# SCH_TrailCheaper_2024-05-25.net
KiCad netlist of a schematic drawn in EasyEDA
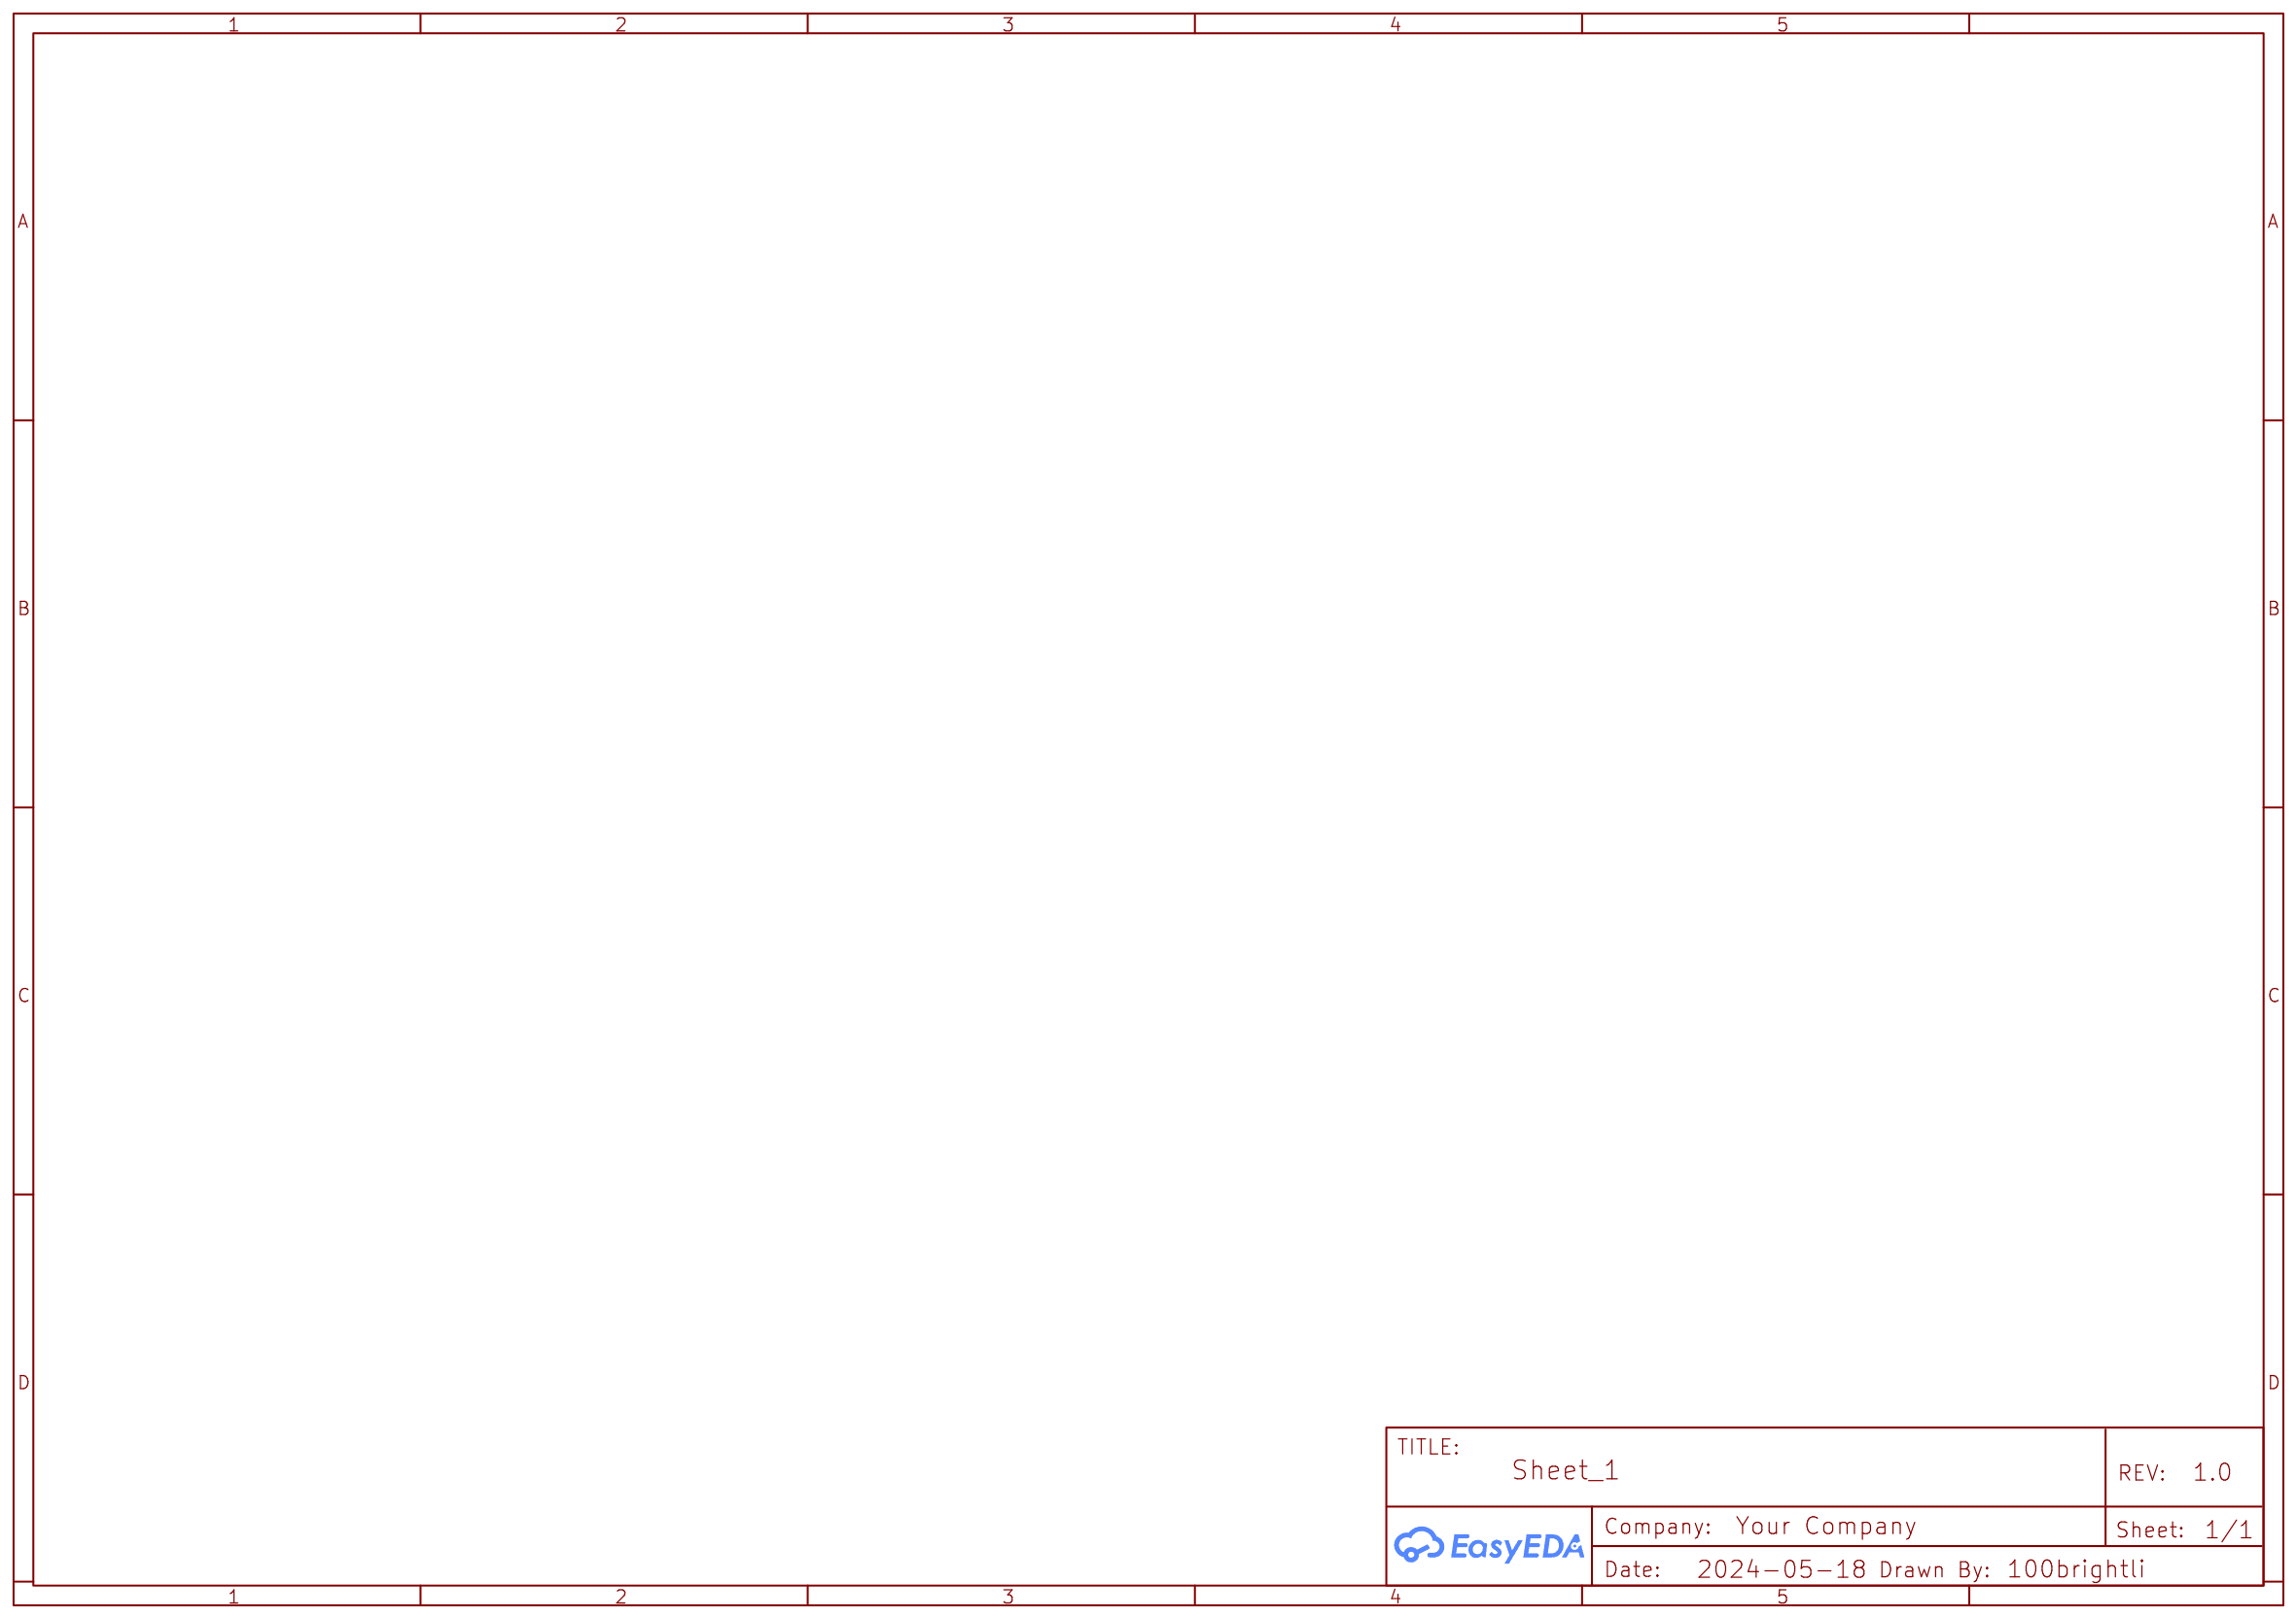
[diagram p0: Sheet_1]
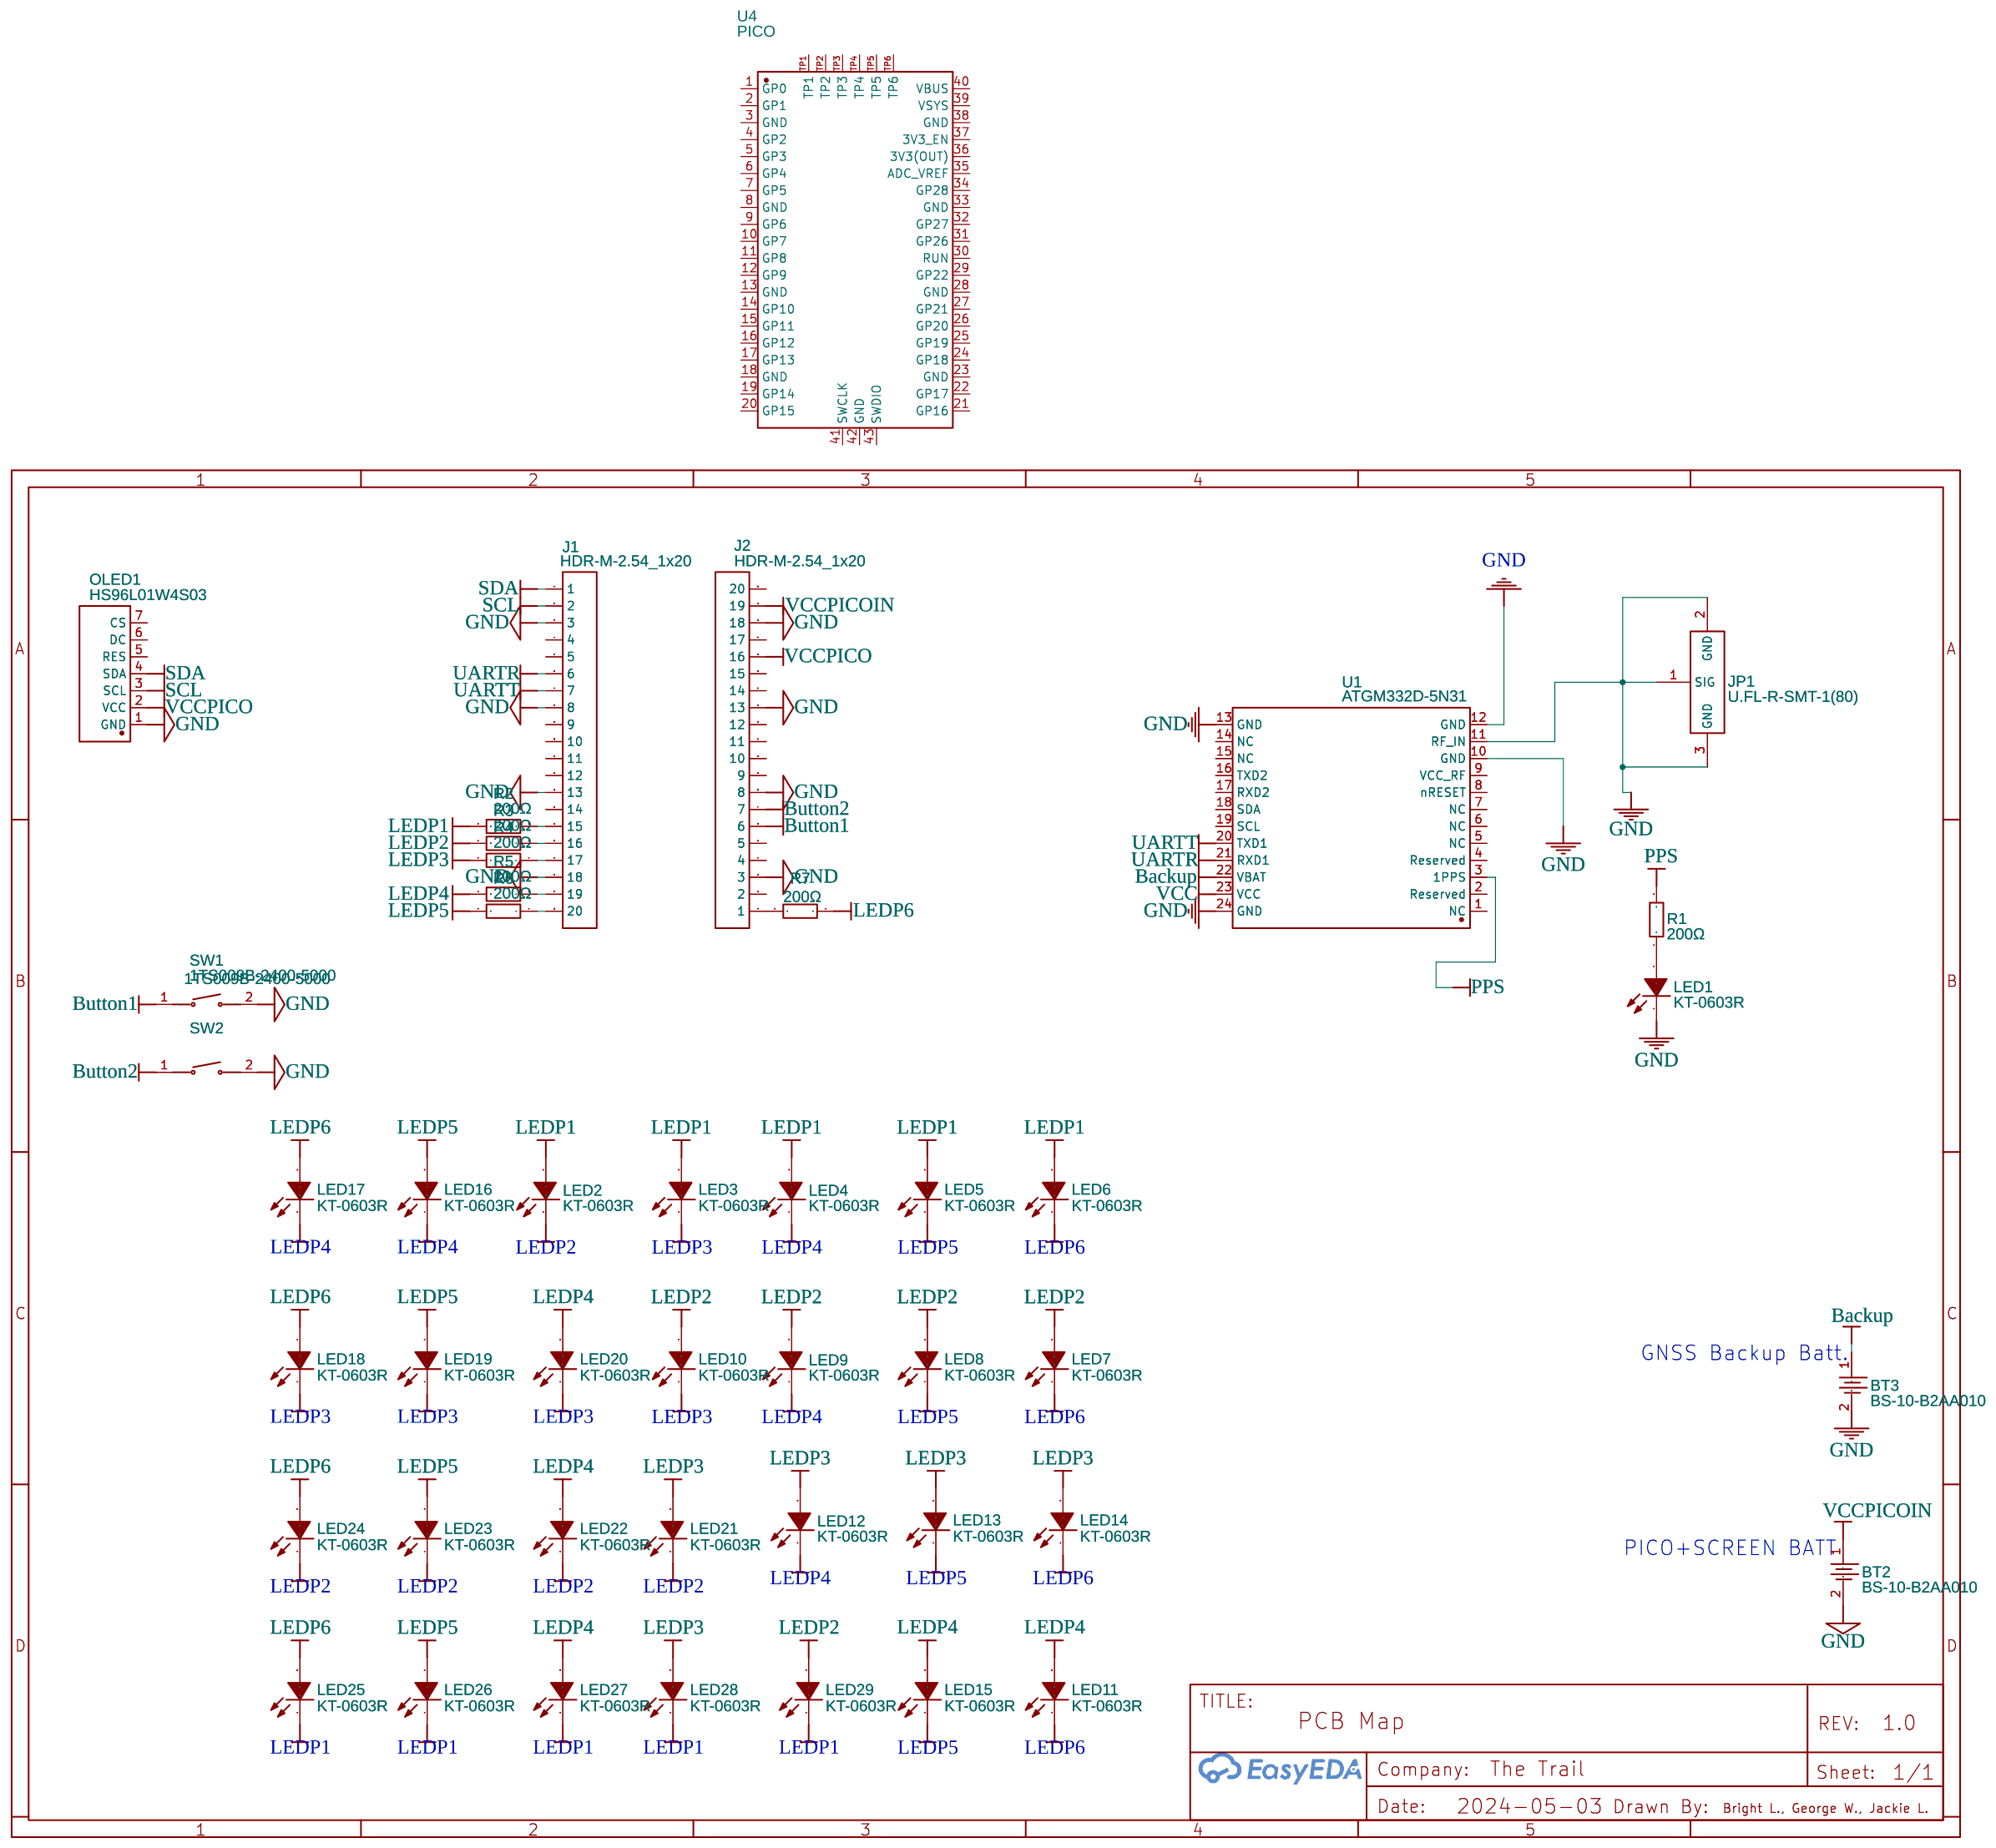
[diagram p1: Sheet_2_Cheaper? copy]

(export (version "E")
  (design (tool "Eeschema 10.0.6"))
  (components
    (comp (ref "BT2")
      (value "BS-10-B2AA010")
      (fields (field (name "Manufacturer") "MYOUNG(美阳)"))
      (libsource (lib "") (part "BS-10-B2AA010"))
    )
    (comp (ref "BT3")
      (value "BS-10-B2AA010")
      (fields (field (name "Manufacturer") "MYOUNG(美阳)"))
      (libsource (lib "") (part "BS-10-B2AA010"))
    )
    (comp (ref "J1") (value "HDR-M-2.54_1x20") (libsource (lib "") (part "HDR-M-2.54_1x20")))
    (comp (ref "J2") (value "HDR-M-2.54_1x20") (libsource (lib "") (part "HDR-M-2.54_1x20_1")))
    (comp (ref "JP1")
      (value "U.FL-R-SMT-1(80)")
      (fields (field (name "Manufacturer") "HRS(广濑)"))
      (libsource (lib "") (part "U.FL-R-SMT-1(80)"))
    )
    (comp (ref "LED1")
      (value "KT-0603R")
      (fields (field (name "Manufacturer") "KENTO"))
      (libsource (lib "") (part "KT-0603R"))
    )
    (comp (ref "LED2")
      (value "KT-0603R")
      (fields (field (name "Manufacturer") "KENTO"))
      (libsource (lib "") (part "KT-0603R"))
    )
    (comp (ref "LED3")
      (value "KT-0603R")
      (fields (field (name "Manufacturer") "KENTO"))
      (libsource (lib "") (part "KT-0603R"))
    )
    (comp (ref "LED4")
      (value "KT-0603R")
      (fields (field (name "Manufacturer") "KENTO"))
      (libsource (lib "") (part "KT-0603R"))
    )
    (comp (ref "LED5")
      (value "KT-0603R")
      (fields (field (name "Manufacturer") "KENTO"))
      (libsource (lib "") (part "KT-0603R"))
    )
    (comp (ref "LED6")
      (value "KT-0603R")
      (fields (field (name "Manufacturer") "KENTO"))
      (libsource (lib "") (part "KT-0603R"))
    )
    (comp (ref "LED7")
      (value "KT-0603R")
      (fields (field (name "Manufacturer") "KENTO"))
      (libsource (lib "") (part "KT-0603R"))
    )
    (comp (ref "LED8")
      (value "KT-0603R")
      (fields (field (name "Manufacturer") "KENTO"))
      (libsource (lib "") (part "KT-0603R"))
    )
    (comp (ref "LED9")
      (value "KT-0603R")
      (fields (field (name "Manufacturer") "KENTO"))
      (libsource (lib "") (part "KT-0603R"))
    )
    (comp (ref "LED10")
      (value "KT-0603R")
      (fields (field (name "Manufacturer") "KENTO"))
      (libsource (lib "") (part "KT-0603R"))
    )
    (comp (ref "LED11")
      (value "KT-0603R")
      (fields (field (name "Manufacturer") "KENTO"))
      (libsource (lib "") (part "KT-0603R"))
    )
    (comp (ref "LED12")
      (value "KT-0603R")
      (fields (field (name "Manufacturer") "KENTO"))
      (libsource (lib "") (part "KT-0603R"))
    )
    (comp (ref "LED13")
      (value "KT-0603R")
      (fields (field (name "Manufacturer") "KENTO"))
      (libsource (lib "") (part "KT-0603R"))
    )
    (comp (ref "LED14")
      (value "KT-0603R")
      (fields (field (name "Manufacturer") "KENTO"))
      (libsource (lib "") (part "KT-0603R"))
    )
    (comp (ref "LED15")
      (value "KT-0603R")
      (fields (field (name "Manufacturer") "KENTO"))
      (libsource (lib "") (part "KT-0603R"))
    )
    (comp (ref "LED16")
      (value "KT-0603R")
      (fields (field (name "Manufacturer") "KENTO"))
      (libsource (lib "") (part "KT-0603R"))
    )
    (comp (ref "LED17")
      (value "KT-0603R")
      (fields (field (name "Manufacturer") "KENTO"))
      (libsource (lib "") (part "KT-0603R"))
    )
    (comp (ref "LED18")
      (value "KT-0603R")
      (fields (field (name "Manufacturer") "KENTO"))
      (libsource (lib "") (part "KT-0603R"))
    )
    (comp (ref "LED19")
      (value "KT-0603R")
      (fields (field (name "Manufacturer") "KENTO"))
      (libsource (lib "") (part "KT-0603R"))
    )
    (comp (ref "LED20")
      (value "KT-0603R")
      (fields (field (name "Manufacturer") "KENTO"))
      (libsource (lib "") (part "KT-0603R"))
    )
    (comp (ref "LED21")
      (value "KT-0603R")
      (fields (field (name "Manufacturer") "KENTO"))
      (libsource (lib "") (part "KT-0603R"))
    )
    (comp (ref "LED22")
      (value "KT-0603R")
      (fields (field (name "Manufacturer") "KENTO"))
      (libsource (lib "") (part "KT-0603R"))
    )
    (comp (ref "LED23")
      (value "KT-0603R")
      (fields (field (name "Manufacturer") "KENTO"))
      (libsource (lib "") (part "KT-0603R"))
    )
    (comp (ref "LED24")
      (value "KT-0603R")
      (fields (field (name "Manufacturer") "KENTO"))
      (libsource (lib "") (part "KT-0603R"))
    )
    (comp (ref "LED25")
      (value "KT-0603R")
      (fields (field (name "Manufacturer") "KENTO"))
      (libsource (lib "") (part "KT-0603R"))
    )
    (comp (ref "LED26")
      (value "KT-0603R")
      (fields (field (name "Manufacturer") "KENTO"))
      (libsource (lib "") (part "KT-0603R"))
    )
    (comp (ref "LED27")
      (value "KT-0603R")
      (fields (field (name "Manufacturer") "KENTO"))
      (libsource (lib "") (part "KT-0603R"))
    )
    (comp (ref "LED28")
      (value "KT-0603R")
      (fields (field (name "Manufacturer") "KENTO"))
      (libsource (lib "") (part "KT-0603R"))
    )
    (comp (ref "LED29")
      (value "KT-0603R")
      (fields (field (name "Manufacturer") "KENTO"))
      (libsource (lib "") (part "KT-0603R"))
    )
    (comp (ref "OLED1")
      (value "HS96L01W4S03")
      (fields (field (name "Manufacturer") "HS(汉昇)"))
      (libsource (lib "") (part "HS96L01W4S03"))
    )
    (comp (ref "R1")
      (value "200Ω")
      (fields
        (field (name "Manufacturer Part") "0402WGF2000TCE")
        (field (name "Manufacturer") "UNI-ROYAL(厚声)")
      )
      (libsource (lib "") (part "0402WGF2000TCE_1"))
    )
    (comp (ref "R2")
      (value "200Ω")
      (fields
        (field (name "Manufacturer Part") "0402WGF2000TCE")
        (field (name "Manufacturer") "UNI-ROYAL(厚声)")
      )
      (libsource (lib "") (part "0402WGF2000TCE"))
    )
    (comp (ref "R3")
      (value "200Ω")
      (fields
        (field (name "Manufacturer Part") "0402WGF2000TCE")
        (field (name "Manufacturer") "UNI-ROYAL(厚声)")
      )
      (libsource (lib "") (part "0402WGF2000TCE"))
    )
    (comp (ref "R4")
      (value "200Ω")
      (fields
        (field (name "Manufacturer Part") "0402WGF2000TCE")
        (field (name "Manufacturer") "UNI-ROYAL(厚声)")
      )
      (libsource (lib "") (part "0402WGF2000TCE"))
    )
    (comp (ref "R5")
      (value "200Ω")
      (fields
        (field (name "Manufacturer Part") "0402WGF2000TCE")
        (field (name "Manufacturer") "UNI-ROYAL(厚声)")
      )
      (libsource (lib "") (part "0402WGF2000TCE"))
    )
    (comp (ref "R6")
      (value "200Ω")
      (fields
        (field (name "Manufacturer Part") "0402WGF2000TCE")
        (field (name "Manufacturer") "UNI-ROYAL(厚声)")
      )
      (libsource (lib "") (part "0402WGF2000TCE"))
    )
    (comp (ref "R7")
      (value "200Ω")
      (fields
        (field (name "Manufacturer Part") "0402WGF2000TCE")
        (field (name "Manufacturer") "UNI-ROYAL(厚声)")
      )
      (libsource (lib "") (part "0402WGF2000TCE"))
    )
    (comp (ref "SW1")
      (value "1TS009B-2400-5000")
      (fields
        (field (name "Manufacturer Part") "1TS009B-2400-5000-CT")
        (field (name "Manufacturer") "HYP(鸿源精密)")
      )
      (libsource (lib "") (part "1TS009B-2400-5000"))
    )
    (comp (ref "SW2")
      (value "1TS009B-2400-5000")
      (fields
        (field (name "Manufacturer Part") "1TS009B-2400-5000-CT")
        (field (name "Manufacturer") "HYP(鸿源精密)")
      )
      (libsource (lib "") (part "1TS009B-2400-5000"))
    )
    (comp (ref "U1")
      (value "ATGM332D-5N31")
      (fields (field (name "Manufacturer") "杭州中科微"))
      (libsource (lib "") (part "ATGM332D-5N31"))
    )
    (comp (ref "U4")
      (value "PICO")
      (fields (field (name "Manufacturer") "Raspberry Pi(树莓派)"))
      (libsource (lib "") (part "PICO"))
    )
  )
  (nets
    (net (code "1") (name "Backup") (class "Default")
      (node (ref "BT3") (pin "1") (pinfunction "1_1") (pintype "input"))
      (node (ref "U1") (pin "22") (pinfunction "VBAT_22") (pintype "unspecified"))
    )
    (net (code "2") (name "Button1") (class "Default")
      (node (ref "J2") (pin "6") (pinfunction "6_6") (pintype "unspecified"))
      (node (ref "SW1") (pin "1") (pinfunction "1_1") (pintype "unspecified"))
    )
    (net (code "3") (name "Button2") (class "Default")
      (node (ref "J2") (pin "7") (pinfunction "7_7") (pintype "unspecified"))
      (node (ref "SW2") (pin "1") (pinfunction "1_1") (pintype "unspecified"))
    )
    (net (code "4") (name "GND") (class "Default")
      (node (ref "BT2") (pin "2") (pinfunction "2_2") (pintype "input"))
      (node (ref "BT3") (pin "2") (pinfunction "2_2") (pintype "input"))
      (node (ref "J1") (pin "13") (pinfunction "13_13") (pintype "unspecified"))
      (node (ref "J1") (pin "18") (pinfunction "18_18") (pintype "unspecified"))
      (node (ref "J1") (pin "3") (pinfunction "3_3") (pintype "unspecified"))
      (node (ref "J1") (pin "8") (pinfunction "8_8") (pintype "unspecified"))
      (node (ref "J2") (pin "13") (pinfunction "13_13") (pintype "unspecified"))
      (node (ref "J2") (pin "18") (pinfunction "18_18") (pintype "unspecified"))
      (node (ref "J2") (pin "3") (pinfunction "3_3") (pintype "unspecified"))
      (node (ref "J2") (pin "8") (pinfunction "8_8") (pintype "unspecified"))
      (node (ref "JP1") (pin "1") (pinfunction "SIG_1") (pintype "unspecified"))
      (node (ref "JP1") (pin "2") (pinfunction "GND_2") (pintype "unspecified"))
      (node (ref "JP1") (pin "3") (pinfunction "GND_3") (pintype "unspecified"))
      (node (ref "LED1") (pin "1") (pinfunction "K_1") (pintype "unspecified"))
      (node (ref "OLED1") (pin "1") (pinfunction "GND_1") (pintype "unspecified"))
      (node (ref "SW1") (pin "2") (pinfunction "2_2") (pintype "unspecified"))
      (node (ref "SW2") (pin "2") (pinfunction "2_2") (pintype "unspecified"))
      (node (ref "U1") (pin "10") (pinfunction "GND_10") (pintype "unspecified"))
      (node (ref "U1") (pin "11") (pinfunction "RF_IN_11") (pintype "unspecified"))
      (node (ref "U1") (pin "12") (pinfunction "GND_12") (pintype "unspecified"))
      (node (ref "U1") (pin "13") (pinfunction "GND_13") (pintype "unspecified"))
      (node (ref "U1") (pin "24") (pinfunction "GND_24") (pintype "unspecified"))
    )
    (net (code "5") (name "LEDP1") (class "Default")
      (node (ref "LED2") (pin "2") (pinfunction "A_2") (pintype "unspecified"))
      (node (ref "LED25") (pin "1") (pinfunction "K_1") (pintype "unspecified"))
      (node (ref "LED26") (pin "1") (pinfunction "K_1") (pintype "unspecified"))
      (node (ref "LED27") (pin "1") (pinfunction "K_1") (pintype "unspecified"))
      (node (ref "LED28") (pin "1") (pinfunction "K_1") (pintype "unspecified"))
      (node (ref "LED29") (pin "1") (pinfunction "K_1") (pintype "unspecified"))
      (node (ref "LED3") (pin "2") (pinfunction "A_2") (pintype "unspecified"))
      (node (ref "LED4") (pin "2") (pinfunction "A_2") (pintype "unspecified"))
      (node (ref "LED5") (pin "2") (pinfunction "A_2") (pintype "unspecified"))
      (node (ref "LED6") (pin "2") (pinfunction "A_2") (pintype "unspecified"))
      (node (ref "R2") (pin "2") (pinfunction "2_2") (pintype "input"))
    )
    (net (code "6") (name "LEDP2") (class "Default")
      (node (ref "LED10") (pin "2") (pinfunction "A_2") (pintype "unspecified"))
      (node (ref "LED2") (pin "1") (pinfunction "K_1") (pintype "unspecified"))
      (node (ref "LED21") (pin "1") (pinfunction "K_1") (pintype "unspecified"))
      (node (ref "LED22") (pin "1") (pinfunction "K_1") (pintype "unspecified"))
      (node (ref "LED23") (pin "1") (pinfunction "K_1") (pintype "unspecified"))
      (node (ref "LED24") (pin "1") (pinfunction "K_1") (pintype "unspecified"))
      (node (ref "LED29") (pin "2") (pinfunction "A_2") (pintype "unspecified"))
      (node (ref "LED7") (pin "2") (pinfunction "A_2") (pintype "unspecified"))
      (node (ref "LED8") (pin "2") (pinfunction "A_2") (pintype "unspecified"))
      (node (ref "LED9") (pin "2") (pinfunction "A_2") (pintype "unspecified"))
      (node (ref "R3") (pin "2") (pinfunction "2_2") (pintype "input"))
    )
    (net (code "7") (name "LEDP3") (class "Default")
      (node (ref "LED10") (pin "1") (pinfunction "K_1") (pintype "unspecified"))
      (node (ref "LED12") (pin "2") (pinfunction "A_2") (pintype "unspecified"))
      (node (ref "LED13") (pin "2") (pinfunction "A_2") (pintype "unspecified"))
      (node (ref "LED14") (pin "2") (pinfunction "A_2") (pintype "unspecified"))
      (node (ref "LED18") (pin "1") (pinfunction "K_1") (pintype "unspecified"))
      (node (ref "LED19") (pin "1") (pinfunction "K_1") (pintype "unspecified"))
      (node (ref "LED20") (pin "1") (pinfunction "K_1") (pintype "unspecified"))
      (node (ref "LED21") (pin "2") (pinfunction "A_2") (pintype "unspecified"))
      (node (ref "LED28") (pin "2") (pinfunction "A_2") (pintype "unspecified"))
      (node (ref "LED3") (pin "1") (pinfunction "K_1") (pintype "unspecified"))
      (node (ref "R4") (pin "2") (pinfunction "2_2") (pintype "input"))
    )
    (net (code "8") (name "LEDP4") (class "Default")
      (node (ref "LED11") (pin "2") (pinfunction "A_2") (pintype "unspecified"))
      (node (ref "LED12") (pin "1") (pinfunction "K_1") (pintype "unspecified"))
      (node (ref "LED15") (pin "2") (pinfunction "A_2") (pintype "unspecified"))
      (node (ref "LED16") (pin "1") (pinfunction "K_1") (pintype "unspecified"))
      (node (ref "LED17") (pin "1") (pinfunction "K_1") (pintype "unspecified"))
      (node (ref "LED20") (pin "2") (pinfunction "A_2") (pintype "unspecified"))
      (node (ref "LED22") (pin "2") (pinfunction "A_2") (pintype "unspecified"))
      (node (ref "LED27") (pin "2") (pinfunction "A_2") (pintype "unspecified"))
      (node (ref "LED4") (pin "1") (pinfunction "K_1") (pintype "unspecified"))
      (node (ref "LED9") (pin "1") (pinfunction "K_1") (pintype "unspecified"))
      (node (ref "R5") (pin "2") (pinfunction "2_2") (pintype "input"))
    )
    (net (code "9") (name "LEDP5") (class "Default")
      (node (ref "LED13") (pin "1") (pinfunction "K_1") (pintype "unspecified"))
      (node (ref "LED15") (pin "1") (pinfunction "K_1") (pintype "unspecified"))
      (node (ref "LED16") (pin "2") (pinfunction "A_2") (pintype "unspecified"))
      (node (ref "LED19") (pin "2") (pinfunction "A_2") (pintype "unspecified"))
      (node (ref "LED23") (pin "2") (pinfunction "A_2") (pintype "unspecified"))
      (node (ref "LED26") (pin "2") (pinfunction "A_2") (pintype "unspecified"))
      (node (ref "LED5") (pin "1") (pinfunction "K_1") (pintype "unspecified"))
      (node (ref "LED8") (pin "1") (pinfunction "K_1") (pintype "unspecified"))
      (node (ref "R6") (pin "2") (pinfunction "2_2") (pintype "input"))
    )
    (net (code "10") (name "LEDP6") (class "Default")
      (node (ref "LED11") (pin "1") (pinfunction "K_1") (pintype "unspecified"))
      (node (ref "LED14") (pin "1") (pinfunction "K_1") (pintype "unspecified"))
      (node (ref "LED17") (pin "2") (pinfunction "A_2") (pintype "unspecified"))
      (node (ref "LED18") (pin "2") (pinfunction "A_2") (pintype "unspecified"))
      (node (ref "LED24") (pin "2") (pinfunction "A_2") (pintype "unspecified"))
      (node (ref "LED25") (pin "2") (pinfunction "A_2") (pintype "unspecified"))
      (node (ref "LED6") (pin "1") (pinfunction "K_1") (pintype "unspecified"))
      (node (ref "LED7") (pin "1") (pinfunction "K_1") (pintype "unspecified"))
      (node (ref "R7") (pin "1") (pinfunction "1_1") (pintype "input"))
    )
    (net (code "11") (name "Net-(J1-Pad15)") (class "Default")
      (node (ref "J1") (pin "15") (pinfunction "15_15") (pintype "unspecified"))
      (node (ref "R2") (pin "1") (pinfunction "1_1") (pintype "input"))
    )
    (net (code "12") (name "Net-(J1-Pad16)") (class "Default")
      (node (ref "J1") (pin "16") (pinfunction "16_16") (pintype "unspecified"))
      (node (ref "R3") (pin "1") (pinfunction "1_1") (pintype "input"))
    )
    (net (code "13") (name "Net-(J1-Pad17)") (class "Default")
      (node (ref "J1") (pin "17") (pinfunction "17_17") (pintype "unspecified"))
      (node (ref "R4") (pin "1") (pinfunction "1_1") (pintype "input"))
    )
    (net (code "14") (name "Net-(J1-Pad19)") (class "Default")
      (node (ref "J1") (pin "19") (pinfunction "19_19") (pintype "unspecified"))
      (node (ref "R5") (pin "1") (pinfunction "1_1") (pintype "input"))
    )
    (net (code "15") (name "Net-(J1-Pad20)") (class "Default")
      (node (ref "J1") (pin "20") (pinfunction "20_20") (pintype "unspecified"))
      (node (ref "R6") (pin "1") (pinfunction "1_1") (pintype "input"))
    )
    (net (code "16") (name "Net-(J2-Pad1)") (class "Default")
      (node (ref "J2") (pin "1") (pinfunction "1_1") (pintype "unspecified"))
      (node (ref "R7") (pin "2") (pinfunction "2_2") (pintype "input"))
    )
    (net (code "17") (name "Net-(LED1-A)") (class "Default")
      (node (ref "LED1") (pin "2") (pinfunction "A_2") (pintype "unspecified"))
      (node (ref "R1") (pin "1") (pinfunction "1_1") (pintype "input"))
    )
    (net (code "18") (name "PPS") (class "Default")
      (node (ref "R1") (pin "2") (pinfunction "2_2") (pintype "input"))
      (node (ref "U1") (pin "3") (pinfunction "1PPS_3") (pintype "unspecified"))
    )
    (net (code "19") (name "SCL") (class "Default")
      (node (ref "J1") (pin "2") (pinfunction "2_2") (pintype "unspecified"))
      (node (ref "OLED1") (pin "3") (pinfunction "SCL_3") (pintype "unspecified"))
    )
    (net (code "20") (name "SDA") (class "Default")
      (node (ref "J1") (pin "1") (pinfunction "1_1") (pintype "unspecified"))
      (node (ref "OLED1") (pin "4") (pinfunction "SDA_4") (pintype "unspecified"))
    )
    (net (code "21") (name "UARTR") (class "Default")
      (node (ref "J1") (pin "6") (pinfunction "6_6") (pintype "unspecified"))
      (node (ref "U1") (pin "21") (pinfunction "RXD1_21") (pintype "unspecified"))
    )
    (net (code "22") (name "UARTT") (class "Default")
      (node (ref "J1") (pin "7") (pinfunction "7_7") (pintype "unspecified"))
      (node (ref "U1") (pin "20") (pinfunction "TXD1_20") (pintype "unspecified"))
    )
    (net (code "23") (name "VCC") (class "Default")
      (node (ref "U1") (pin "23") (pinfunction "VCC_23") (pintype "unspecified"))
    )
    (net (code "24") (name "VCCPICO") (class "Default")
      (node (ref "J2") (pin "16") (pinfunction "16_16") (pintype "unspecified"))
      (node (ref "OLED1") (pin "2") (pinfunction "VCC_2") (pintype "unspecified"))
    )
    (net (code "25") (name "VCCPICOIN") (class "Default")
      (node (ref "BT2") (pin "1") (pinfunction "1_1") (pintype "input"))
      (node (ref "J2") (pin "19") (pinfunction "19_19") (pintype "unspecified"))
    )
    (net (code "26") (name "unconnected-(J1-Pad4)") (class "Default")
      (node (ref "J1") (pin "4") (pinfunction "4_4") (pintype "unspecified"))
    )
    (net (code "27") (name "unconnected-(J1-Pad5)") (class "Default")
      (node (ref "J1") (pin "5") (pinfunction "5_5") (pintype "unspecified"))
    )
    (net (code "28") (name "unconnected-(J1-Pad9)") (class "Default")
      (node (ref "J1") (pin "9") (pinfunction "9_9") (pintype "unspecified"))
    )
    (net (code "29") (name "unconnected-(J1-Pad10)") (class "Default")
      (node (ref "J1") (pin "10") (pinfunction "10_10") (pintype "unspecified"))
    )
    (net (code "30") (name "unconnected-(J1-Pad11)") (class "Default")
      (node (ref "J1") (pin "11") (pinfunction "11_11") (pintype "unspecified"))
    )
    (net (code "31") (name "unconnected-(J1-Pad12)") (class "Default")
      (node (ref "J1") (pin "12") (pinfunction "12_12") (pintype "unspecified"))
    )
    (net (code "32") (name "unconnected-(J1-Pad14)") (class "Default")
      (node (ref "J1") (pin "14") (pinfunction "14_14") (pintype "unspecified"))
    )
    (net (code "33") (name "unconnected-(J2-Pad2)") (class "Default")
      (node (ref "J2") (pin "2") (pinfunction "2_2") (pintype "unspecified"))
    )
    (net (code "34") (name "unconnected-(J2-Pad4)") (class "Default")
      (node (ref "J2") (pin "4") (pinfunction "4_4") (pintype "unspecified"))
    )
    (net (code "35") (name "unconnected-(J2-Pad5)") (class "Default")
      (node (ref "J2") (pin "5") (pinfunction "5_5") (pintype "unspecified"))
    )
    (net (code "36") (name "unconnected-(J2-Pad9)") (class "Default")
      (node (ref "J2") (pin "9") (pinfunction "9_9") (pintype "unspecified"))
    )
    (net (code "37") (name "unconnected-(J2-Pad10)") (class "Default")
      (node (ref "J2") (pin "10") (pinfunction "10_10") (pintype "unspecified"))
    )
    (net (code "38") (name "unconnected-(J2-Pad11)") (class "Default")
      (node (ref "J2") (pin "11") (pinfunction "11_11") (pintype "unspecified"))
    )
    (net (code "39") (name "unconnected-(J2-Pad12)") (class "Default")
      (node (ref "J2") (pin "12") (pinfunction "12_12") (pintype "unspecified"))
    )
    (net (code "40") (name "unconnected-(J2-Pad14)") (class "Default")
      (node (ref "J2") (pin "14") (pinfunction "14_14") (pintype "unspecified"))
    )
    (net (code "41") (name "unconnected-(J2-Pad15)") (class "Default")
      (node (ref "J2") (pin "15") (pinfunction "15_15") (pintype "unspecified"))
    )
    (net (code "42") (name "unconnected-(J2-Pad17)") (class "Default")
      (node (ref "J2") (pin "17") (pinfunction "17_17") (pintype "unspecified"))
    )
    (net (code "43") (name "unconnected-(J2-Pad20)") (class "Default")
      (node (ref "J2") (pin "20") (pinfunction "20_20") (pintype "unspecified"))
    )
    (net (code "44") (name "unconnected-(OLED1-CS-Pad7)") (class "Default")
      (node (ref "OLED1") (pin "7") (pinfunction "CS_7") (pintype "unspecified"))
    )
    (net (code "45") (name "unconnected-(OLED1-DC-Pad6)") (class "Default")
      (node (ref "OLED1") (pin "6") (pinfunction "DC_6") (pintype "unspecified"))
    )
    (net (code "46") (name "unconnected-(OLED1-RES-Pad5)") (class "Default")
      (node (ref "OLED1") (pin "5") (pinfunction "RES_5") (pintype "unspecified"))
    )
    (net (code "47") (name "unconnected-(U1-NC-Pad1)") (class "Default")
      (node (ref "U1") (pin "1") (pinfunction "NC_1") (pintype "unspecified"))
    )
    (net (code "48") (name "unconnected-(U1-NC-Pad5)") (class "Default")
      (node (ref "U1") (pin "5") (pinfunction "NC_5") (pintype "unspecified"))
    )
    (net (code "49") (name "unconnected-(U1-NC-Pad6)") (class "Default")
      (node (ref "U1") (pin "6") (pinfunction "NC_6") (pintype "unspecified"))
    )
    (net (code "50") (name "unconnected-(U1-NC-Pad7)") (class "Default")
      (node (ref "U1") (pin "7") (pinfunction "NC_7") (pintype "unspecified"))
    )
    (net (code "51") (name "unconnected-(U1-NC-Pad14)") (class "Default")
      (node (ref "U1") (pin "14") (pinfunction "NC_14") (pintype "unspecified"))
    )
    (net (code "52") (name "unconnected-(U1-NC-Pad15)") (class "Default")
      (node (ref "U1") (pin "15") (pinfunction "NC_15") (pintype "unspecified"))
    )
    (net (code "53") (name "unconnected-(U1-RXD2-Pad17)") (class "Default")
      (node (ref "U1") (pin "17") (pinfunction "RXD2_17") (pintype "unspecified"))
    )
    (net (code "54") (name "unconnected-(U1-Reserved-Pad2)") (class "Default")
      (node (ref "U1") (pin "2") (pinfunction "Reserved_2") (pintype "unspecified"))
    )
    (net (code "55") (name "unconnected-(U1-Reserved-Pad4)") (class "Default")
      (node (ref "U1") (pin "4") (pinfunction "Reserved_4") (pintype "unspecified"))
    )
    (net (code "56") (name "unconnected-(U1-SCL-Pad19)") (class "Default")
      (node (ref "U1") (pin "19") (pinfunction "SCL_19") (pintype "unspecified"))
    )
    (net (code "57") (name "unconnected-(U1-SDA-Pad18)") (class "Default")
      (node (ref "U1") (pin "18") (pinfunction "SDA_18") (pintype "unspecified"))
    )
    (net (code "58") (name "unconnected-(U1-TXD2-Pad16)") (class "Default")
      (node (ref "U1") (pin "16") (pinfunction "TXD2_16") (pintype "unspecified"))
    )
    (net (code "59") (name "unconnected-(U1-VCC_RF-Pad9)") (class "Default")
      (node (ref "U1") (pin "9") (pinfunction "VCC_RF_9") (pintype "unspecified"))
    )
    (net (code "60") (name "unconnected-(U1-nRESET-Pad8)") (class "Default")
      (node (ref "U1") (pin "8") (pinfunction "nRESET_8") (pintype "unspecified"))
    )
    (net (code "61") (name "unconnected-(U4-3V3(OUT)-Pad36)") (class "Default")
      (node (ref "U4") (pin "36") (pinfunction "3V3(OUT)_36") (pintype "unspecified"))
    )
    (net (code "62") (name "unconnected-(U4-3V3_EN-Pad37)") (class "Default")
      (node (ref "U4") (pin "37") (pinfunction "3V3_EN_37") (pintype "unspecified"))
    )
    (net (code "63") (name "unconnected-(U4-ADC_VREF-Pad35)") (class "Default")
      (node (ref "U4") (pin "35") (pinfunction "ADC_VREF_35") (pintype "unspecified"))
    )
    (net (code "64") (name "unconnected-(U4-GND-Pad3)") (class "Default")
      (node (ref "U4") (pin "3") (pinfunction "GND_3") (pintype "unspecified"))
    )
    (net (code "65") (name "unconnected-(U4-GND-Pad8)") (class "Default")
      (node (ref "U4") (pin "8") (pinfunction "GND_8") (pintype "unspecified"))
    )
    (net (code "66") (name "unconnected-(U4-GND-Pad13)") (class "Default")
      (node (ref "U4") (pin "13") (pinfunction "GND_13") (pintype "unspecified"))
    )
    (net (code "67") (name "unconnected-(U4-GND-Pad18)") (class "Default")
      (node (ref "U4") (pin "18") (pinfunction "GND_18") (pintype "unspecified"))
    )
    (net (code "68") (name "unconnected-(U4-GND-Pad23)") (class "Default")
      (node (ref "U4") (pin "23") (pinfunction "GND_23") (pintype "unspecified"))
    )
    (net (code "69") (name "unconnected-(U4-GND-Pad28)") (class "Default")
      (node (ref "U4") (pin "28") (pinfunction "GND_28") (pintype "unspecified"))
    )
    (net (code "70") (name "unconnected-(U4-GND-Pad33)") (class "Default")
      (node (ref "U4") (pin "33") (pinfunction "GND_33") (pintype "unspecified"))
    )
    (net (code "71") (name "unconnected-(U4-GND-Pad38)") (class "Default")
      (node (ref "U4") (pin "38") (pinfunction "GND_38") (pintype "unspecified"))
    )
    (net (code "72") (name "unconnected-(U4-GND-Pad42)") (class "Default")
      (node (ref "U4") (pin "42") (pinfunction "GND_42") (pintype "unspecified"))
    )
    (net (code "73") (name "unconnected-(U4-GP0-Pad1)") (class "Default")
      (node (ref "U4") (pin "1") (pinfunction "GP0_1") (pintype "unspecified"))
    )
    (net (code "74") (name "unconnected-(U4-GP1-Pad2)") (class "Default")
      (node (ref "U4") (pin "2") (pinfunction "GP1_2") (pintype "unspecified"))
    )
    (net (code "75") (name "unconnected-(U4-GP2-Pad4)") (class "Default")
      (node (ref "U4") (pin "4") (pinfunction "GP2_4") (pintype "unspecified"))
    )
    (net (code "76") (name "unconnected-(U4-GP3-Pad5)") (class "Default")
      (node (ref "U4") (pin "5") (pinfunction "GP3_5") (pintype "unspecified"))
    )
    (net (code "77") (name "unconnected-(U4-GP4-Pad6)") (class "Default")
      (node (ref "U4") (pin "6") (pinfunction "GP4_6") (pintype "unspecified"))
    )
    (net (code "78") (name "unconnected-(U4-GP5-Pad7)") (class "Default")
      (node (ref "U4") (pin "7") (pinfunction "GP5_7") (pintype "unspecified"))
    )
    (net (code "79") (name "unconnected-(U4-GP6-Pad9)") (class "Default")
      (node (ref "U4") (pin "9") (pinfunction "GP6_9") (pintype "unspecified"))
    )
    (net (code "80") (name "unconnected-(U4-GP7-Pad10)") (class "Default")
      (node (ref "U4") (pin "10") (pinfunction "GP7_10") (pintype "unspecified"))
    )
    (net (code "81") (name "unconnected-(U4-GP8-Pad11)") (class "Default")
      (node (ref "U4") (pin "11") (pinfunction "GP8_11") (pintype "unspecified"))
    )
    (net (code "82") (name "unconnected-(U4-GP9-Pad12)") (class "Default")
      (node (ref "U4") (pin "12") (pinfunction "GP9_12") (pintype "unspecified"))
    )
    (net (code "83") (name "unconnected-(U4-GP10-Pad14)") (class "Default")
      (node (ref "U4") (pin "14") (pinfunction "GP10_14") (pintype "unspecified"))
    )
    (net (code "84") (name "unconnected-(U4-GP11-Pad15)") (class "Default")
      (node (ref "U4") (pin "15") (pinfunction "GP11_15") (pintype "unspecified"))
    )
    (net (code "85") (name "unconnected-(U4-GP12-Pad16)") (class "Default")
      (node (ref "U4") (pin "16") (pinfunction "GP12_16") (pintype "unspecified"))
    )
    (net (code "86") (name "unconnected-(U4-GP13-Pad17)") (class "Default")
      (node (ref "U4") (pin "17") (pinfunction "GP13_17") (pintype "unspecified"))
    )
    (net (code "87") (name "unconnected-(U4-GP14-Pad19)") (class "Default")
      (node (ref "U4") (pin "19") (pinfunction "GP14_19") (pintype "unspecified"))
    )
    (net (code "88") (name "unconnected-(U4-GP15-Pad20)") (class "Default")
      (node (ref "U4") (pin "20") (pinfunction "GP15_20") (pintype "unspecified"))
    )
    (net (code "89") (name "unconnected-(U4-GP16-Pad21)") (class "Default")
      (node (ref "U4") (pin "21") (pinfunction "GP16_21") (pintype "unspecified"))
    )
    (net (code "90") (name "unconnected-(U4-GP17-Pad22)") (class "Default")
      (node (ref "U4") (pin "22") (pinfunction "GP17_22") (pintype "unspecified"))
    )
    (net (code "91") (name "unconnected-(U4-GP18-Pad24)") (class "Default")
      (node (ref "U4") (pin "24") (pinfunction "GP18_24") (pintype "unspecified"))
    )
    (net (code "92") (name "unconnected-(U4-GP19-Pad25)") (class "Default")
      (node (ref "U4") (pin "25") (pinfunction "GP19_25") (pintype "unspecified"))
    )
    (net (code "93") (name "unconnected-(U4-GP20-Pad26)") (class "Default")
      (node (ref "U4") (pin "26") (pinfunction "GP20_26") (pintype "unspecified"))
    )
    (net (code "94") (name "unconnected-(U4-GP21-Pad27)") (class "Default")
      (node (ref "U4") (pin "27") (pinfunction "GP21_27") (pintype "unspecified"))
    )
    (net (code "95") (name "unconnected-(U4-GP22-Pad29)") (class "Default")
      (node (ref "U4") (pin "29") (pinfunction "GP22_29") (pintype "unspecified"))
    )
    (net (code "96") (name "unconnected-(U4-GP26-Pad31)") (class "Default")
      (node (ref "U4") (pin "31") (pinfunction "GP26_31") (pintype "unspecified"))
    )
    (net (code "97") (name "unconnected-(U4-GP27-Pad32)") (class "Default")
      (node (ref "U4") (pin "32") (pinfunction "GP27_32") (pintype "unspecified"))
    )
    (net (code "98") (name "unconnected-(U4-GP28-Pad34)") (class "Default")
      (node (ref "U4") (pin "34") (pinfunction "GP28_34") (pintype "unspecified"))
    )
    (net (code "99") (name "unconnected-(U4-PadTP1)") (class "Default")
      (node (ref "U4") (pin "TP1") (pinfunction "TP1_TP1") (pintype "unspecified"))
    )
    (net (code "100") (name "unconnected-(U4-PadTP2)") (class "Default")
      (node (ref "U4") (pin "TP2") (pinfunction "TP2_TP2") (pintype "unspecified"))
    )
    (net (code "101") (name "unconnected-(U4-PadTP3)") (class "Default")
      (node (ref "U4") (pin "TP3") (pinfunction "TP3_TP3") (pintype "unspecified"))
    )
    (net (code "102") (name "unconnected-(U4-PadTP4)") (class "Default")
      (node (ref "U4") (pin "TP4") (pinfunction "TP4_TP4") (pintype "unspecified"))
    )
    (net (code "103") (name "unconnected-(U4-PadTP5)") (class "Default")
      (node (ref "U4") (pin "TP5") (pinfunction "TP5_TP5") (pintype "unspecified"))
    )
    (net (code "104") (name "unconnected-(U4-PadTP6)") (class "Default")
      (node (ref "U4") (pin "TP6") (pinfunction "TP6_TP6") (pintype "unspecified"))
    )
    (net (code "105") (name "unconnected-(U4-RUN-Pad30)") (class "Default")
      (node (ref "U4") (pin "30") (pinfunction "RUN_30") (pintype "unspecified"))
    )
    (net (code "106") (name "unconnected-(U4-SWCLK-Pad41)") (class "Default")
      (node (ref "U4") (pin "41") (pinfunction "SWCLK_41") (pintype "unspecified"))
    )
    (net (code "107") (name "unconnected-(U4-SWDIO-Pad43)") (class "Default")
      (node (ref "U4") (pin "43") (pinfunction "SWDIO_43") (pintype "unspecified"))
    )
    (net (code "108") (name "unconnected-(U4-VBUS-Pad40)") (class "Default")
      (node (ref "U4") (pin "40") (pinfunction "VBUS_40") (pintype "unspecified"))
    )
    (net (code "109") (name "unconnected-(U4-VSYS-Pad39)") (class "Default")
      (node (ref "U4") (pin "39") (pinfunction "VSYS_39") (pintype "unspecified"))
    )
  )
)
